# 3_USB.net
KiCad netlist of a schematic drawn in Altium Designer
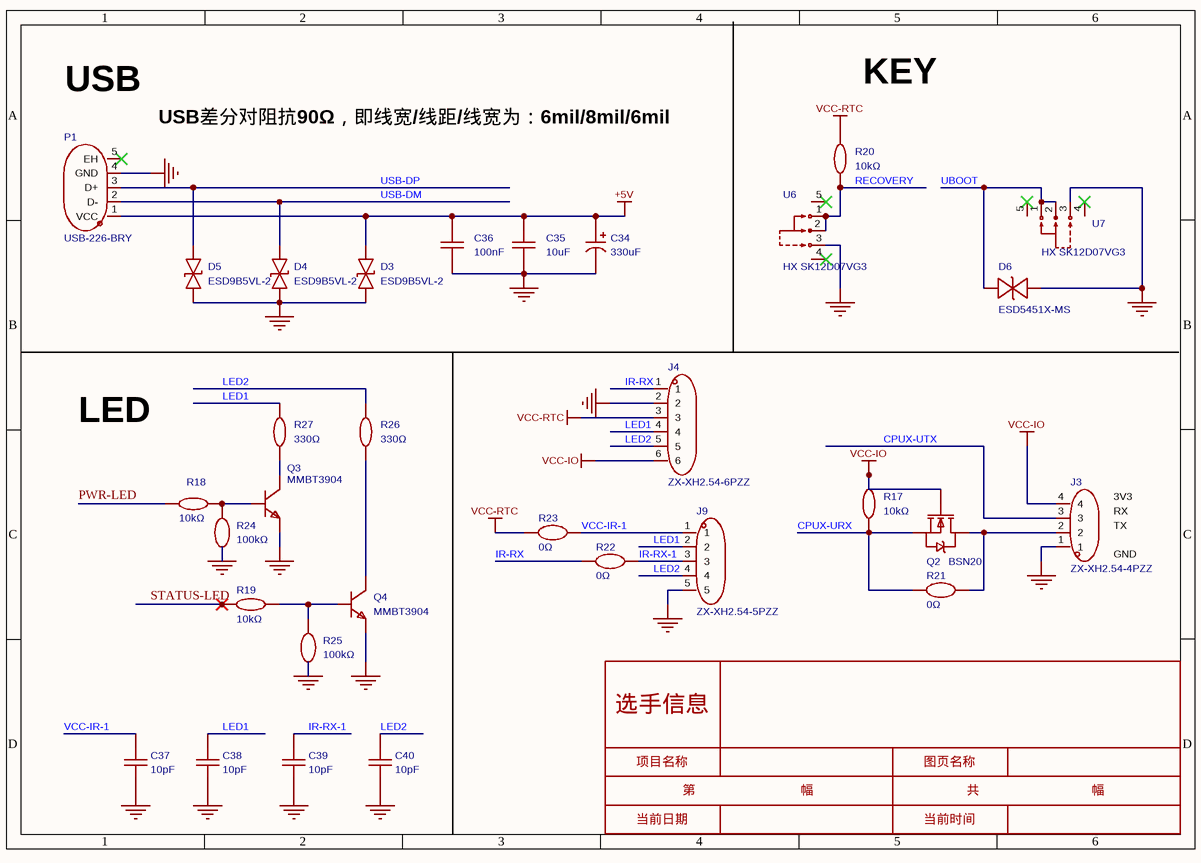
[diagram p0: 3_USB.schdoc]

(export (version "E")
  (design (tool "Eeschema 10.0.6"))
  (components
    (comp (ref "C34")
      (value "330uF")
      (footprint "CAP-TH_BD6.3-P2.50-D0.6-FD-3")
      (description "容值:330uF;精度:±20%;额定电压:16V;纹波电流:4.1A@100kHz;等效串联电阻(ESR):16mΩ@100kHz;类型:聚合物;")
      (fields (field (name "MANUFACTURER") "JIERR(捷而瑞)") (field (name "MANUFACTURERPART") "PB16V330M6X11"))
      (libsource (lib "altium-import") (part "root_3_PB16V330M6X11_"))
    )
    (comp (ref "C35")
      (value "10uF")
      (footprint "C0805")
      (description "容值:10uF;精度:±10%;额定电压:50V;温度系数:X5R;")
      (fields (field (name "MANUFACTURER") "HRE(芯声)") (field (name "MANUFACTURERPART") "CGA0805X5R106K500MT"))
      (libsource (lib "altium-import") (part "root_1_CGA0805X5R106K500MT_"))
    )
    (comp (ref "C36")
      (value "100nF")
      (footprint "C0402")
      (description "容值:100nF;精度:±10%;额定电压:16V;温度系数:X7R;")
      (fields (field (name "MANUFACTURER") "SAMSUNG(三星)") (field (name "MANUFACTURERPART") "CL05B104KO5NNNC"))
      (libsource (lib "altium-import") (part "root_1_CL05B104KO5NNNC_"))
    )
    (comp (ref "C37")
      (value "10pF")
      (footprint "C0402")
      (description "容值:10pF;精度:±5%;额定电压:50V;温度系数:C0G;")
      (fields
        (field (name "MANUFACTURER") "SAMSUNG(三星)")
        (field (name "MANUFACTURER PART") "CL05C100JB5NNNC")
      )
      (libsource (lib "altium-import") (part "root_1_CL05C100JB5NNNC_"))
    )
    (comp (ref "C38")
      (value "10pF")
      (footprint "C0402")
      (description "容值:10pF;精度:±5%;额定电压:50V;温度系数:C0G;")
      (fields
        (field (name "MANUFACTURER") "SAMSUNG(三星)")
        (field (name "MANUFACTURER PART") "CL05C100JB5NNNC")
      )
      (libsource (lib "altium-import") (part "root_1_CL05C100JB5NNNC_"))
    )
    (comp (ref "C39")
      (value "10pF")
      (footprint "C0402")
      (description "容值:10pF;精度:±5%;额定电压:50V;温度系数:C0G;")
      (fields
        (field (name "MANUFACTURER") "SAMSUNG(三星)")
        (field (name "MANUFACTURER PART") "CL05C100JB5NNNC")
      )
      (libsource (lib "altium-import") (part "root_1_CL05C100JB5NNNC_"))
    )
    (comp (ref "C40")
      (value "10pF")
      (footprint "C0402")
      (description "容值:10pF;精度:±5%;额定电压:50V;温度系数:C0G;")
      (fields
        (field (name "MANUFACTURER") "SAMSUNG(三星)")
        (field (name "MANUFACTURER PART") "CL05C100JB5NNNC")
      )
      (libsource (lib "altium-import") (part "root_1_CL05C100JB5NNNC_"))
    )
    (comp (ref "D3")
      (value "ESD9B5VL-2")
      (footprint "DFN1006-2L-BI")
      (description "反向截止电压(Vrwm):5V;钳位电压:12.5V;峰值脉冲功率(Ppp):80W@8/20us;击穿电压:6V;")
      (fields (field (name "MANUFACTURER") "Leiditech(雷卯电子)"))
      (libsource (lib "altium-import") (part "root_1_ESD9B5VL-2_"))
    )
    (comp (ref "D4")
      (value "ESD9B5VL-2")
      (footprint "DFN1006-2L-BI")
      (description "反向截止电压(Vrwm):5V;钳位电压:12.5V;峰值脉冲功率(Ppp):80W@8/20us;击穿电压:6V;")
      (fields (field (name "MANUFACTURER") "Leiditech(雷卯电子)"))
      (libsource (lib "altium-import") (part "root_1_ESD9B5VL-2_"))
    )
    (comp (ref "D5")
      (value "ESD9B5VL-2")
      (footprint "DFN1006-2L-BI")
      (description "反向截止电压(Vrwm):5V;钳位电压:12.5V;峰值脉冲功率(Ppp):80W@8/20us;击穿电压:6V;")
      (fields (field (name "MANUFACTURER") "Leiditech(雷卯电子)"))
      (libsource (lib "altium-import") (part "root_1_ESD9B5VL-2_"))
    )
    (comp (ref "D6")
      (value "ESD5451X-MS")
      (footprint "DFN1006-2L-BI")
      (description "反向截止电压(Vrwm):5V;峰值脉冲电流(Ipp):8A;击穿电压:5.6V;")
      (fields (field (name "MANUFACTURER") "MSKSEMI(美森科)"))
      (libsource (lib "altium-import") (part "root_0_ESD5451X-MS_"))
    )
    (comp (ref "J3")
      (value "ZX-XH2.54-4PZZ")
      (footprint "CONN-TH_4P-P2.50_4PIN")
      (fields (field (name "MANUFACTURER") "Megastar(兆星)"))
      (libsource (lib "altium-import") (part "root_2_mirrored_ZX-XH2.54-4PZZ_"))
    )
    (comp (ref "J4")
      (value "ZX-XH2.54-6PZZ")
      (footprint "CONN-TH_6P-P2.50_ZX-XH2.54-6PZZ")
      (fields (field (name "MANUFACTURER") "Megastar(兆星)"))
      (libsource (lib "altium-import") (part "root_0_ZX-XH2.54-6PZZ_"))
    )
    (comp (ref "J9")
      (value "ZX-XH2.54-5PZZ")
      (footprint "CONN-TH_5P-P2.50_ZX-XH2.54-5PZZ")
      (fields (field (name "MANUFACTURER") "Megastar(兆星)"))
      (libsource (lib "altium-import") (part "root_0_ZX-XH2.54-5PZZ_"))
    )
    (comp (ref "P1")
      (value "USB-226-BRY")
      (footprint "USB-A-TH_USB-226-BRY")
      (description "连接器类型:Type-A;协议标准:USB 2.0;公母:母;安装方式:侧插;触点数量:4P;端口数量:1;额定电流 - 电源:1.5A;工作温度:-20℃~+70℃;")
      (fields (field (name "MANUFACTURER") "XUNPU(讯普)"))
      (libsource (lib "altium-import") (part "root_2_USB-226-BRY_"))
    )
    (comp (ref "Q2")
      (value "BSN20")
      (footprint "SOT-23-3_L2.9-W1.6-P1.90-LS2.8-BR")
      (fields (field (name "MANUFACTURER") "SHIKUES(时科)"))
      (libsource (lib "altium-import") (part "root_3_BSN20_C116157_"))
    )
    (comp (ref "Q3")
      (value "MMBT3904")
      (footprint "SOT-23-3_L2.9-W1.3-P1.90-LS2.4-BR")
      (description "晶体管类型:NPN;集电极电流(Ic):200mA;集射极击穿电压(Vceo):40V;耗散功率(Pd):200mW;直流电流增益(hFE):100@10mA,1.0V;")
      (fields (field (name "MANUFACTURER") "R+O(宏嘉诚)"))
      (libsource (lib "altium-import") (part "root_0_MMBT3904_C7420353_"))
    )
    (comp (ref "Q4")
      (value "MMBT3904")
      (footprint "SOT-23-3_L2.9-W1.3-P1.90-LS2.4-BR")
      (description "晶体管类型:NPN;集电极电流(Ic):200mA;集射极击穿电压(Vceo):40V;耗散功率(Pd):200mW;直流电流增益(hFE):100@10mA,1.0V;")
      (fields (field (name "MANUFACTURER") "R+O(宏嘉诚)"))
      (libsource (lib "altium-import") (part "root_0_MMBT3904_C7420353_"))
    )
    (comp (ref "R17")
      (value "10kΩ")
      (footprint "R0402")
      (description "电阻类型:厚膜电阻;阻值:10kΩ;精度:±1%;功率:62.5mW;工作电压:50V;温度系数:±100ppm/℃;")
      (fields (field (name "MANUFACTURER") "YAGEO(国巨)") (field (name "MANUFACTURER PART") "RC0402FR-0710KL"))
      (libsource (lib "altium-import") (part "root_1_RC0402FR-0710KL_"))
    )
    (comp (ref "R18")
      (value "10kΩ")
      (footprint "R0402")
      (description "电阻类型:厚膜电阻;阻值:10kΩ;精度:±1%;功率:62.5mW;工作电压:50V;温度系数:±100ppm/℃;")
      (fields (field (name "MANUFACTURER") "YAGEO(国巨)") (field (name "MANUFACTURER PART") "RC0402FR-0710KL"))
      (libsource (lib "altium-import") (part "root_0_RC0402FR-0710KL_"))
    )
    (comp (ref "R19")
      (value "10kΩ")
      (footprint "R0402")
      (description "电阻类型:厚膜电阻;阻值:10kΩ;精度:±1%;功率:62.5mW;工作电压:50V;温度系数:±100ppm/℃;")
      (fields (field (name "MANUFACTURER") "YAGEO(国巨)") (field (name "MANUFACTURER PART") "RC0402FR-0710KL"))
      (libsource (lib "altium-import") (part "root_0_RC0402FR-0710KL_"))
    )
    (comp (ref "R20")
      (value "10kΩ")
      (footprint "R0402")
      (description "电阻类型:厚膜电阻;阻值:10kΩ;精度:±1%;功率:62.5mW;工作电压:50V;温度系数:±100ppm/℃;")
      (fields (field (name "MANUFACTURER") "YAGEO(国巨)") (field (name "MANUFACTURER PART") "RC0402FR-0710KL"))
      (libsource (lib "altium-import") (part "root_1_RC0402FR-0710KL_"))
    )
    (comp (ref "R21")
      (value "0Ω")
      (footprint "R0402")
      (description "电阻类型:厚膜电阻;阻值:0Ω;精度:±5%;功率:62.5mW;工作电压:50V;")
      (fields (field (name "MANUFACTURER") "FOJAN(富捷)") (field (name "MANUFACTURER PART") "FRC0402P000 TS"))
      (libsource (lib "altium-import") (part "root_0_FRC0402P000 TS_"))
    )
    (comp (ref "R22")
      (value "0Ω")
      (footprint "R0402")
      (description "电阻类型:厚膜电阻;阻值:0Ω;精度:±5%;功率:62.5mW;工作电压:50V;")
      (fields (field (name "MANUFACTURER") "FOJAN(富捷)") (field (name "MANUFACTURER PART") "FRC0402P000 TS"))
      (libsource (lib "altium-import") (part "root_0_FRC0402P000 TS_"))
    )
    (comp (ref "R23")
      (value "0Ω")
      (footprint "R0402")
      (description "电阻类型:厚膜电阻;阻值:0Ω;精度:±5%;功率:62.5mW;工作电压:50V;")
      (fields (field (name "MANUFACTURER") "FOJAN(富捷)") (field (name "MANUFACTURER PART") "FRC0402P000 TS"))
      (libsource (lib "altium-import") (part "root_0_FRC0402P000 TS_"))
    )
    (comp (ref "R24")
      (value "100kΩ")
      (footprint "R0402")
      (description "电阻类型:薄膜电阻;阻值:100kΩ;精度:±0.1%;功率:62.5mW;最大工作电压:50V;温度系数:±25ppm/℃;")
      (fields (field (name "MANUFACTURER") "YAGEO(国巨)") (field (name "MANUFACTURER PART") "RT0402BRD07100KL"))
      (libsource (lib "altium-import") (part "root_1_RT0402BRD07100KL_"))
    )
    (comp (ref "R25")
      (value "100kΩ")
      (footprint "R0402")
      (description "电阻类型:薄膜电阻;阻值:100kΩ;精度:±0.1%;功率:62.5mW;最大工作电压:50V;温度系数:±25ppm/℃;")
      (fields (field (name "MANUFACTURER") "YAGEO(国巨)") (field (name "MANUFACTURER PART") "RT0402BRD07100KL"))
      (libsource (lib "altium-import") (part "root_1_RT0402BRD07100KL_"))
    )
    (comp (ref "R26")
      (value "330Ω")
      (footprint "R0402")
      (description "电阻类型:厚膜电阻;阻值:330Ω;精度:±1%;功率:62.5mW;工作电压:50V;温度系数:±100ppm/℃;")
      (fields
        (field (name "MANUFACTURER") "UNI-ROYAL(厚声)")
        (field (name "MANUFACTURER PART") "0402WGF3300TCE")
      )
      (libsource (lib "altium-import") (part "root_1_0402WGF3300TCE_"))
    )
    (comp (ref "R27")
      (value "330Ω")
      (footprint "R0402")
      (description "电阻类型:厚膜电阻;阻值:330Ω;精度:±1%;功率:62.5mW;工作电压:50V;温度系数:±100ppm/℃;")
      (fields
        (field (name "MANUFACTURER") "UNI-ROYAL(厚声)")
        (field (name "MANUFACTURER PART") "0402WGF3300TCE")
      )
      (libsource (lib "altium-import") (part "root_1_0402WGF3300TCE_"))
    )
    (comp (ref "U6")
      (value "HX SK12D07VG3")
      (footprint "SW-TH_SK12D07VG3")
      (description "电路结构:单刀双掷;安装方式:弯插;开关颜色:黑色;额定电流:300mA;额定电压:50V;工作寿命:8千次;")
      (fields (field (name "MANUFACTURER") "hanxia(韩下)"))
      (libsource (lib "altium-import") (part "root_2_mirrored_HX SK12D07VG3_"))
    )
    (comp (ref "U7")
      (value "HX SK12D07VG3")
      (footprint "SW-TH_SK12D07VG3")
      (description "电路结构:单刀双掷;安装方式:弯插;开关颜色:黑色;额定电流:300mA;额定电压:50V;工作寿命:8千次;")
      (fields (field (name "MANUFACTURER") "hanxia(韩下)"))
      (libsource (lib "altium-import") (part "root_1_mirrored_HX SK12D07VG3_"))
    )
  )
  (nets
    (net (code "1") (name "+5V") (class "Default")
      (node (ref "C34") (pin "1") (pinfunction "1_1") (pintype "passive"))
      (node (ref "C35") (pin "2") (pinfunction "2_2") (pintype "passive"))
      (node (ref "C36") (pin "2") (pinfunction "2_2") (pintype "passive"))
      (node (ref "D3") (pin "2") (pinfunction "2_2") (pintype "passive"))
      (node (ref "P1") (pin "1") (pinfunction "VCC_1") (pintype "passive"))
    )
    (net (code "3") (name "/CPUX-URX") (class "Default")
      (node (ref "Q2") (pin "2") (pinfunction "S_2") (pintype "passive"))
      (node (ref "R17") (pin "1") (pinfunction "1_1") (pintype "passive"))
      (node (ref "R21") (pin "1") (pinfunction "1_1") (pintype "passive"))
    )
    (net (code "4") (name "/CPUX-UTX") (class "Default")
      (node (ref "J3") (pin "3") (pinfunction "3_3") (pintype "passive"))
    )
    (net (code "5") (name "/IR-RX") (class "Default")
      (node (ref "J4") (pin "1") (pinfunction "1_1") (pintype "passive"))
      (node (ref "R22") (pin "1") (pinfunction "1_1") (pintype "passive"))
    )
    (net (code "6") (name "/IR-RX-1") (class "Default")
      (node (ref "C39") (pin "2") (pinfunction "2_2") (pintype "passive"))
      (node (ref "J9") (pin "3") (pinfunction "3_3") (pintype "passive"))
      (node (ref "R22") (pin "2") (pinfunction "2_2") (pintype "passive"))
    )
    (net (code "7") (name "/LED1") (class "Default")
      (node (ref "C38") (pin "2") (pinfunction "2_2") (pintype "passive"))
      (node (ref "J4") (pin "4") (pinfunction "4_4") (pintype "passive"))
      (node (ref "J9") (pin "2") (pinfunction "2_2") (pintype "passive"))
      (node (ref "R27") (pin "2") (pinfunction "2_2") (pintype "passive"))
    )
    (net (code "8") (name "/LED2") (class "Default")
      (node (ref "C40") (pin "2") (pinfunction "2_2") (pintype "passive"))
      (node (ref "J4") (pin "5") (pinfunction "5_5") (pintype "passive"))
      (node (ref "J9") (pin "4") (pinfunction "4_4") (pintype "passive"))
      (node (ref "R26") (pin "2") (pinfunction "2_2") (pintype "passive"))
    )
    (net (code "9") (name "/PWR-LED") (class "Default")
      (node (ref "R18") (pin "1") (pinfunction "1_1") (pintype "passive"))
    )
    (net (code "10") (name "/RECOVERY") (class "Default")
      (node (ref "R20") (pin "1") (pinfunction "1_1") (pintype "passive"))
      (node (ref "U6") (pin "1") (pinfunction "1_1") (pintype "passive"))
      (node (ref "U6") (pin "2") (pinfunction "2_2") (pintype "passive"))
    )
    (net (code "11") (name "/STATUS-LED") (class "Default")
      (node (ref "R19") (pin "1") (pinfunction "1_1") (pintype "passive+no_connect"))
    )
    (net (code "12") (name "/UBOOT") (class "Default")
      (node (ref "D6") (pin "1") (pinfunction "1_1") (pintype "passive"))
      (node (ref "U7") (pin "1") (pinfunction "1_1") (pintype "passive"))
      (node (ref "U7") (pin "2") (pinfunction "2_2") (pintype "passive"))
    )
    (net (code "13") (name "/USB-DM") (class "Default")
      (node (ref "D4") (pin "2") (pinfunction "2_2") (pintype "passive"))
      (node (ref "P1") (pin "2") (pinfunction "D-_2") (pintype "passive"))
    )
    (net (code "14") (name "/USB-DP") (class "Default")
      (node (ref "D5") (pin "2") (pinfunction "2_2") (pintype "passive"))
      (node (ref "P1") (pin "3") (pinfunction "D+_3") (pintype "passive"))
    )
    (net (code "15") (name "/VCC-IR-1") (class "Default")
      (node (ref "C37") (pin "2") (pinfunction "2_2") (pintype "passive"))
      (node (ref "J9") (pin "1") (pinfunction "1_1") (pintype "passive"))
      (node (ref "R23") (pin "2") (pinfunction "2_2") (pintype "passive"))
    )
    (net (code "16") (name "GND") (class "Default")
      (node (ref "C34") (pin "2") (pinfunction "2_2") (pintype "passive"))
      (node (ref "C35") (pin "1") (pinfunction "1_1") (pintype "passive"))
      (node (ref "C36") (pin "1") (pinfunction "1_1") (pintype "passive"))
      (node (ref "C37") (pin "1") (pinfunction "1_1") (pintype "passive"))
      (node (ref "C38") (pin "1") (pinfunction "1_1") (pintype "passive"))
      (node (ref "C39") (pin "1") (pinfunction "1_1") (pintype "passive"))
      (node (ref "C40") (pin "1") (pinfunction "1_1") (pintype "passive"))
      (node (ref "D3") (pin "1") (pinfunction "1_1") (pintype "passive"))
      (node (ref "D4") (pin "1") (pinfunction "1_1") (pintype "passive"))
      (node (ref "D5") (pin "1") (pinfunction "1_1") (pintype "passive"))
      (node (ref "D6") (pin "2") (pinfunction "2_2") (pintype "passive"))
      (node (ref "J3") (pin "1") (pinfunction "1_1") (pintype "passive"))
      (node (ref "J4") (pin "2") (pinfunction "2_2") (pintype "passive"))
      (node (ref "J9") (pin "5") (pinfunction "5_5") (pintype "passive"))
      (node (ref "P1") (pin "4") (pinfunction "GND_4") (pintype "passive"))
      (node (ref "Q3") (pin "2") (pinfunction "E_2") (pintype "passive"))
      (node (ref "Q4") (pin "2") (pinfunction "E_2") (pintype "passive"))
      (node (ref "R24") (pin "1") (pinfunction "1_1") (pintype "passive"))
      (node (ref "R25") (pin "1") (pinfunction "1_1") (pintype "passive"))
      (node (ref "U6") (pin "3") (pinfunction "3_3") (pintype "passive"))
      (node (ref "U7") (pin "3") (pinfunction "3_3") (pintype "passive"))
    )
    (net (code "17") (name "Net-(Q2-D)") (class "Default")
      (node (ref "J3") (pin "2") (pinfunction "2_2") (pintype "passive"))
      (node (ref "Q2") (pin "3") (pinfunction "D_3") (pintype "passive"))
      (node (ref "R21") (pin "2") (pinfunction "2_2") (pintype "passive"))
    )
    (net (code "18") (name "Net-(Q3-B)") (class "Default")
      (node (ref "Q3") (pin "1") (pinfunction "B_1") (pintype "passive"))
      (node (ref "R18") (pin "2") (pinfunction "2_2") (pintype "passive"))
      (node (ref "R24") (pin "2") (pinfunction "2_2") (pintype "passive"))
    )
    (net (code "19") (name "Net-(Q3-C)") (class "Default")
      (node (ref "Q3") (pin "3") (pinfunction "C_3") (pintype "passive"))
      (node (ref "R27") (pin "1") (pinfunction "1_1") (pintype "passive"))
    )
    (net (code "20") (name "Net-(Q4-B)") (class "Default")
      (node (ref "Q4") (pin "1") (pinfunction "B_1") (pintype "passive"))
      (node (ref "R19") (pin "2") (pinfunction "2_2") (pintype "passive"))
      (node (ref "R25") (pin "2") (pinfunction "2_2") (pintype "passive"))
    )
    (net (code "21") (name "Net-(Q4-C)") (class "Default")
      (node (ref "Q4") (pin "3") (pinfunction "C_3") (pintype "passive"))
      (node (ref "R26") (pin "1") (pinfunction "1_1") (pintype "passive"))
    )
    (net (code "22") (name "VCC-IO") (class "Default")
      (node (ref "J3") (pin "4") (pinfunction "4_4") (pintype "passive"))
      (node (ref "J4") (pin "6") (pinfunction "6_6") (pintype "passive"))
      (node (ref "Q2") (pin "1") (pinfunction "G_1") (pintype "passive"))
      (node (ref "R17") (pin "2") (pinfunction "2_2") (pintype "passive"))
    )
    (net (code "23") (name "VCC-RTC") (class "Default")
      (node (ref "J4") (pin "3") (pinfunction "3_3") (pintype "passive"))
      (node (ref "R20") (pin "2") (pinfunction "2_2") (pintype "passive"))
      (node (ref "R23") (pin "1") (pinfunction "1_1") (pintype "passive"))
    )
    (net (code "24") (name "unconnected-(P1-EH-Pad5)") (class "Default")
      (node (ref "P1") (pin "5") (pinfunction "EH_5") (pintype "passive+no_connect"))
    )
    (net (code "25") (name "unconnected-(U6-Pad4)") (class "Default")
      (node (ref "U6") (pin "4") (pinfunction "4_4") (pintype "passive+no_connect"))
    )
    (net (code "26") (name "unconnected-(U6-Pad5)") (class "Default")
      (node (ref "U6") (pin "5") (pinfunction "5_5") (pintype "passive+no_connect"))
    )
    (net (code "27") (name "unconnected-(U7-Pad4)") (class "Default")
      (node (ref "U7") (pin "4") (pinfunction "4_4") (pintype "passive+no_connect"))
    )
    (net (code "28") (name "unconnected-(U7-Pad5)") (class "Default")
      (node (ref "U7") (pin "5") (pinfunction "5_5") (pintype "passive+no_connect"))
    )
  )
)
